# imu_shield.net
KiCad netlist of a schematic drawn in EAGLE
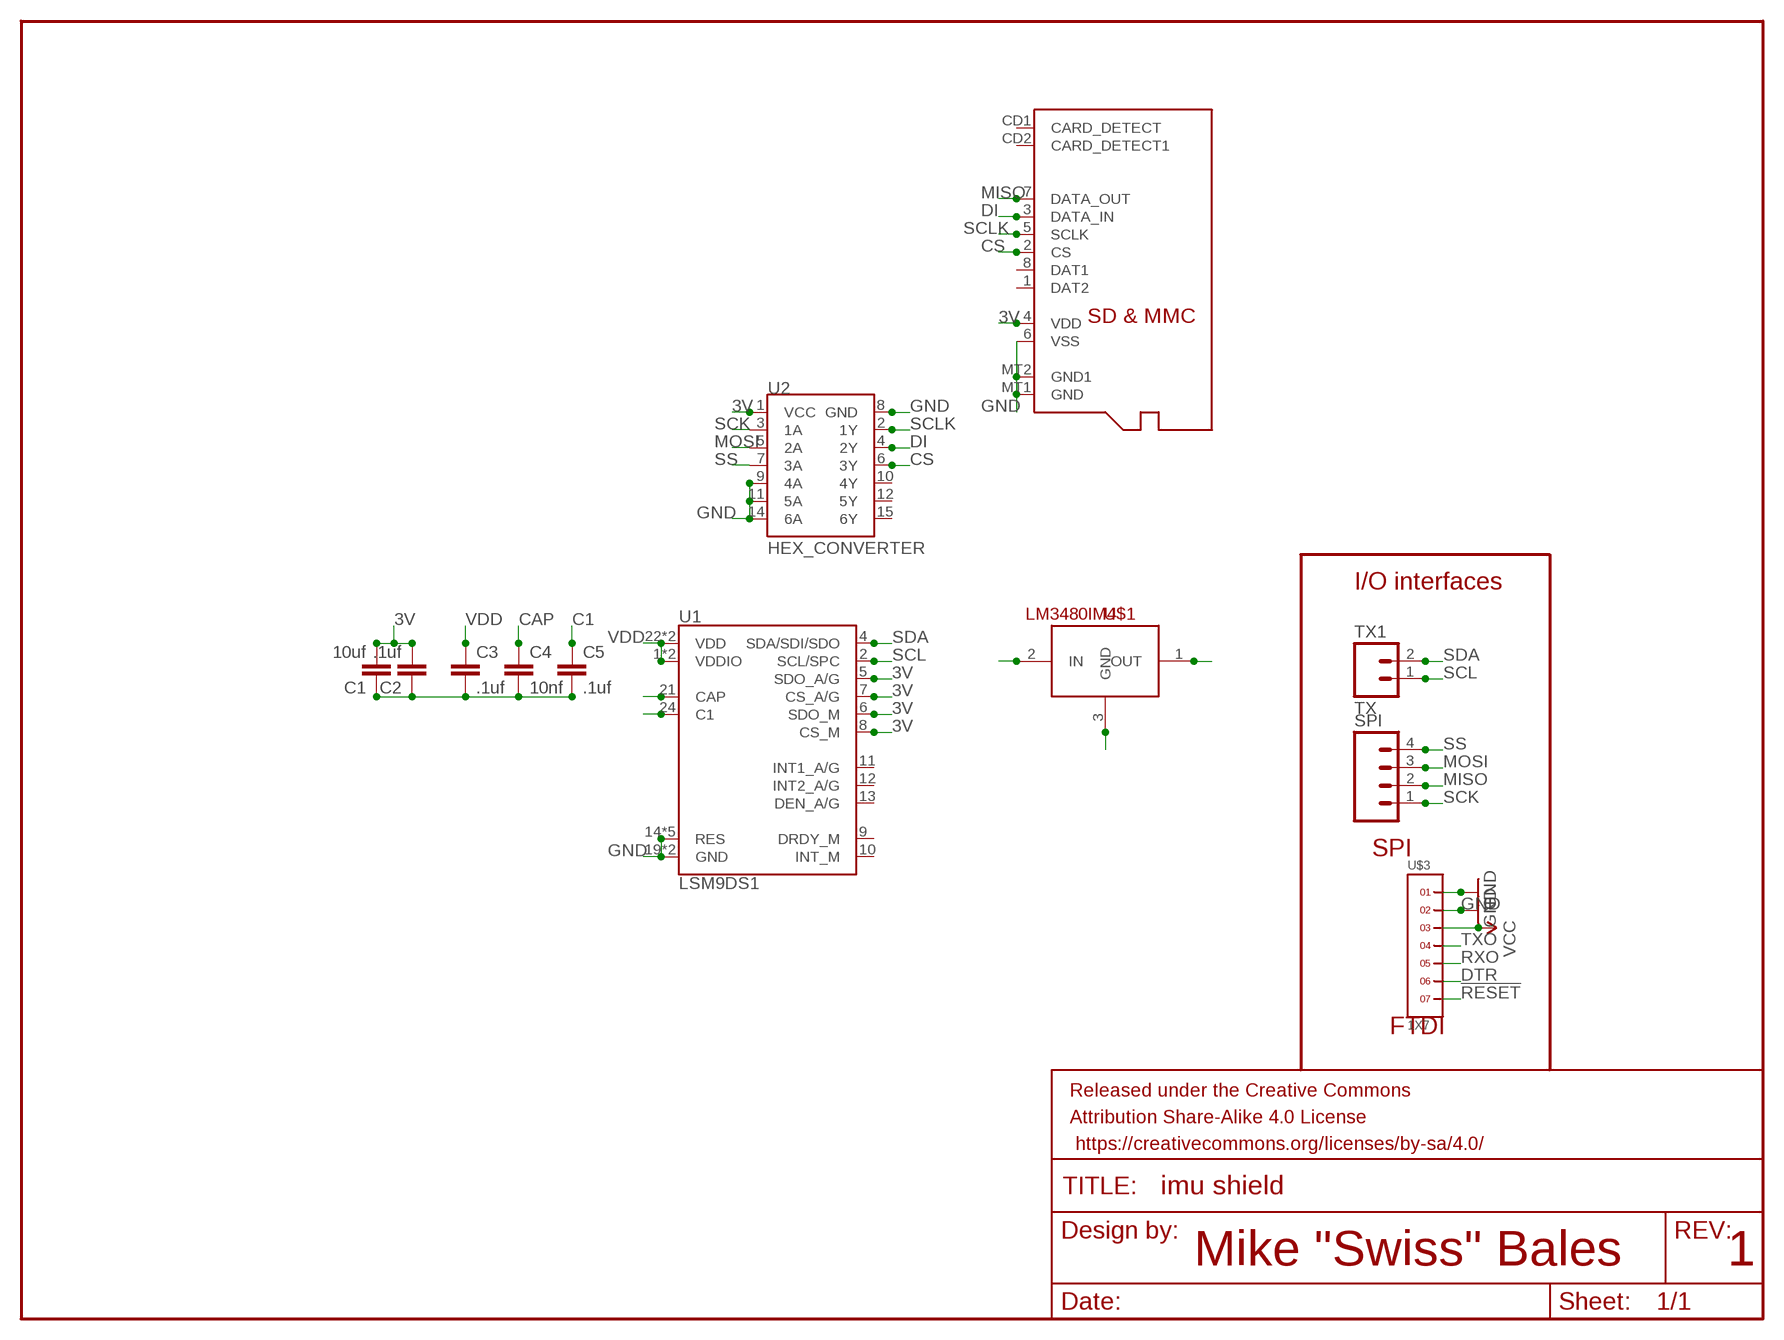
[diagram p0: schematic, sheet 1]

(export (version "E")
  (design (tool "Eeschema 10.0.6"))
  (components
    (comp (ref "C1")
      (value "10uf")
      (footprint "eagle-import:0805")
      (libsource (lib "eagle-import") (part "CAP0805"))
    )
    (comp (ref "C2")
      (value ".1uf")
      (footprint "eagle-import:0805")
      (libsource (lib "eagle-import") (part "CAP0805"))
    )
    (comp (ref "C3")
      (value ".1uf")
      (footprint "eagle-import:0805")
      (libsource (lib "eagle-import") (part "CAP0805"))
    )
    (comp (ref "C4")
      (value "10nf")
      (footprint "eagle-import:0805")
      (libsource (lib "eagle-import") (part "CAP0805"))
    )
    (comp (ref "C5")
      (value ".1uf")
      (footprint "eagle-import:0805")
      (libsource (lib "eagle-import") (part "CAP0805"))
    )
    (comp (ref "FRAME1")
      (value "FRAME-LETTER")
      (footprint "eagle-import:CREATIVE_COMMONS")
      (libsource (lib "eagle-import") (part "FRAME-LETTER"))
    )
    (comp (ref "SPI")
      (value "M04JST-PTH-VERT")
      (footprint "eagle-import:JST-4-PTH-VERT")
      (libsource (lib "eagle-import") (part "M04JST-PTH-VERT"))
    )
    (comp (ref "TX1")
      (value "TX")
      (footprint "eagle-import:JST-2-PTH-VERT")
      (libsource (lib "eagle-import") (part "M02JST-PTH-VERT"))
    )
    (comp (ref "U$1")
      (value "LM3480IM4")
      (footprint "eagle-import:SOT23-3")
      (libsource (lib "eagle-import") (part "LM3480IM4"))
    )
    (comp (ref "U$2")
      (value "MICROSD")
      (footprint "eagle-import:MICROSD")
      (libsource (lib "eagle-import") (part "MICROSD"))
    )
    (comp (ref "U$3")
      (value "1X7")
      (footprint "eagle-import:1X7")
      (libsource (lib "eagle-import") (part "1X7"))
    )
    (comp (ref "U1")
      (value "LSM9DS1")
      (footprint "eagle-import:LGA24-8X4")
      (libsource (lib "eagle-import") (part "LSM9DS1"))
    )
    (comp (ref "U2")
      (value "HEX_CONVERTER")
      (footprint "eagle-import:SO016")
      (libsource (lib "eagle-import") (part "HEX_CONVERTER"))
    )
  )
  (nets
    (net (code "1") (name "/3V") (class "Default")
      (node (ref "C1") (pin "2") (pinfunction "2_2") (pintype "passive"))
      (node (ref "C2") (pin "2") (pinfunction "2_2") (pintype "passive"))
      (node (ref "U$2") (pin "4") (pinfunction "VDD_4") (pintype "power_in"))
      (node (ref "U1") (pin "5") (pinfunction "SDO_A/G_5") (pintype "bidirectional"))
      (node (ref "U1") (pin "6") (pinfunction "SDO_M_6") (pintype "bidirectional"))
      (node (ref "U1") (pin "7") (pinfunction "CS_A/G_7") (pintype "bidirectional"))
      (node (ref "U1") (pin "8") (pinfunction "CS_M_8") (pintype "bidirectional"))
      (node (ref "U2") (pin "1") (pinfunction "VCC_1") (pintype "bidirectional"))
    )
    (net (code "2") (name "/C1") (class "Default")
      (node (ref "C5") (pin "1") (pinfunction "1_1") (pintype "passive"))
      (node (ref "U1") (pin "24") (pinfunction "C1_24") (pintype "bidirectional"))
    )
    (net (code "3") (name "/CAP") (class "Default")
      (node (ref "C4") (pin "1") (pinfunction "1_1") (pintype "passive"))
      (node (ref "U1") (pin "21") (pinfunction "CAP_21") (pintype "bidirectional"))
    )
    (net (code "4") (name "/CS") (class "Default")
      (node (ref "U$2") (pin "2") (pinfunction "CS_2") (pintype "input"))
      (node (ref "U2") (pin "6") (pinfunction "3Y_6") (pintype "bidirectional"))
    )
    (net (code "5") (name "/DI") (class "Default")
      (node (ref "U$2") (pin "3") (pinfunction "DATA_IN_3") (pintype "input"))
      (node (ref "U2") (pin "4") (pinfunction "2Y_4") (pintype "bidirectional"))
    )
    (net (code "6") (name "/DTR") (class "Default")
      (node (ref "U$3") (pin "6") (pinfunction "6_6") (pintype "bidirectional"))
    )
    (net (code "7") (name "/MISO") (class "Default")
      (node (ref "SPI") (pin "2") (pinfunction "2_2") (pintype "passive"))
      (node (ref "U$2") (pin "7") (pinfunction "DATA_OUT_7") (pintype "output"))
    )
    (net (code "8") (name "/MOSI") (class "Default")
      (node (ref "SPI") (pin "3") (pinfunction "3_3") (pintype "passive"))
      (node (ref "U2") (pin "5") (pinfunction "2A_5") (pintype "bidirectional"))
    )
    (net (code "9") (name "/RXO") (class "Default")
      (node (ref "U$3") (pin "5") (pinfunction "5_5") (pintype "bidirectional"))
    )
    (net (code "10") (name "/SCK") (class "Default")
      (node (ref "SPI") (pin "1") (pinfunction "1_1") (pintype "passive"))
      (node (ref "U2") (pin "3") (pinfunction "1A_3") (pintype "bidirectional"))
    )
    (net (code "11") (name "/SCL") (class "Default")
      (node (ref "TX1") (pin "1") (pinfunction "1_1") (pintype "passive"))
      (node (ref "U1") (pin "2") (pinfunction "SCL/SPC_2") (pintype "bidirectional"))
    )
    (net (code "12") (name "/SCLK") (class "Default")
      (node (ref "U$2") (pin "5") (pinfunction "SCLK_5") (pintype "input"))
      (node (ref "U2") (pin "2") (pinfunction "1Y_2") (pintype "bidirectional"))
    )
    (net (code "13") (name "/SDA") (class "Default")
      (node (ref "TX1") (pin "2") (pinfunction "2_2") (pintype "passive"))
      (node (ref "U1") (pin "4") (pinfunction "SDA/SDI/SDO_4") (pintype "bidirectional"))
    )
    (net (code "14") (name "/SS") (class "Default")
      (node (ref "SPI") (pin "4") (pinfunction "4_4") (pintype "passive"))
      (node (ref "U2") (pin "7") (pinfunction "3A_7") (pintype "bidirectional"))
    )
    (net (code "15") (name "/TXO") (class "Default")
      (node (ref "U$3") (pin "4") (pinfunction "4_4") (pintype "bidirectional"))
    )
    (net (code "16") (name "/VDD") (class "Default")
      (node (ref "C3") (pin "1") (pinfunction "1_1") (pintype "passive"))
      (node (ref "U$1") (pin "1") (pinfunction "OUT_1") (pintype "bidirectional"))
      (node (ref "U1") (pin "1") (pinfunction "VDDIO_1") (pintype "bidirectional"))
      (node (ref "U1") (pin "22") (pinfunction "VDD_22") (pintype "bidirectional"))
      (node (ref "U1") (pin "23") (pinfunction "VDD_23") (pintype "bidirectional"))
      (node (ref "U1") (pin "3") (pinfunction "VDDIO_3") (pintype "bidirectional"))
    )
    (net (code "17") (name "/~{RESET}") (class "Default")
      (node (ref "U$3") (pin "7") (pinfunction "7_7") (pintype "bidirectional"))
    )
    (net (code "18") (name "GND") (class "Default")
      (node (ref "U$1") (pin "3") (pinfunction "GND_3") (pintype "bidirectional"))
      (node (ref "U$2") (pin "6") (pinfunction "VSS_6") (pintype "power_in"))
      (node (ref "U$2") (pin "MT1") (pinfunction "GND_MT1") (pintype "power_in"))
      (node (ref "U$2") (pin "MT2") (pinfunction "GND1_MT2") (pintype "power_in"))
      (node (ref "U$3") (pin "1") (pinfunction "1_1") (pintype "bidirectional"))
      (node (ref "U$3") (pin "2") (pinfunction "2_2") (pintype "bidirectional"))
      (node (ref "U1") (pin "14") (pinfunction "RES_14") (pintype "bidirectional"))
      (node (ref "U1") (pin "15") (pinfunction "RES_15") (pintype "bidirectional"))
      (node (ref "U1") (pin "16") (pinfunction "RES_16") (pintype "bidirectional"))
      (node (ref "U1") (pin "17") (pinfunction "RES_17") (pintype "bidirectional"))
      (node (ref "U1") (pin "18") (pinfunction "RES_18") (pintype "bidirectional"))
      (node (ref "U1") (pin "19") (pinfunction "GND_19") (pintype "bidirectional"))
      (node (ref "U1") (pin "20") (pinfunction "GND_20") (pintype "bidirectional"))
      (node (ref "U2") (pin "11") (pinfunction "5A_11") (pintype "bidirectional"))
      (node (ref "U2") (pin "14") (pinfunction "6A_14") (pintype "bidirectional"))
      (node (ref "U2") (pin "8") (pinfunction "GND_8") (pintype "bidirectional"))
      (node (ref "U2") (pin "9") (pinfunction "4A_9") (pintype "bidirectional"))
    )
    (net (code "19") (name "Net-(C1-Pad1)") (class "Default")
      (node (ref "C1") (pin "1") (pinfunction "1_1") (pintype "passive"))
      (node (ref "C2") (pin "1") (pinfunction "1_1") (pintype "passive"))
      (node (ref "C3") (pin "2") (pinfunction "2_2") (pintype "passive"))
      (node (ref "C4") (pin "2") (pinfunction "2_2") (pintype "passive"))
      (node (ref "C5") (pin "2") (pinfunction "2_2") (pintype "passive"))
    )
    (net (code "20") (name "VCC") (class "Default")
      (node (ref "U$1") (pin "2") (pinfunction "IN_2") (pintype "bidirectional"))
      (node (ref "U$3") (pin "3") (pinfunction "3_3") (pintype "bidirectional"))
    )
    (net (code "21") (name "unconnected-(U$2-CARD_DETECT-PadCD1)") (class "Default")
      (node (ref "U$2") (pin "CD1") (pinfunction "CARD_DETECT_CD1") (pintype "passive"))
    )
    (net (code "22") (name "unconnected-(U$2-CARD_DETECT1-PadCD2)") (class "Default")
      (node (ref "U$2") (pin "CD2") (pinfunction "CARD_DETECT1_CD2") (pintype "passive"))
    )
    (net (code "23") (name "unconnected-(U$2-DAT1-Pad8)") (class "Default")
      (node (ref "U$2") (pin "8") (pinfunction "DAT1_8") (pintype "bidirectional"))
    )
    (net (code "24") (name "unconnected-(U$2-DAT2-Pad1)") (class "Default")
      (node (ref "U$2") (pin "1") (pinfunction "DAT2_1") (pintype "bidirectional"))
    )
    (net (code "25") (name "unconnected-(U1-DEN_A{slash}G-Pad13)") (class "Default")
      (node (ref "U1") (pin "13") (pinfunction "DEN_A/G_13") (pintype "bidirectional"))
    )
    (net (code "26") (name "unconnected-(U1-DRDY_M-Pad9)") (class "Default")
      (node (ref "U1") (pin "9") (pinfunction "DRDY_M_9") (pintype "bidirectional"))
    )
    (net (code "27") (name "unconnected-(U1-INT1_A{slash}G-Pad11)") (class "Default")
      (node (ref "U1") (pin "11") (pinfunction "INT1_A/G_11") (pintype "bidirectional"))
    )
    (net (code "28") (name "unconnected-(U1-INT2_A{slash}G-Pad12)") (class "Default")
      (node (ref "U1") (pin "12") (pinfunction "INT2_A/G_12") (pintype "bidirectional"))
    )
    (net (code "29") (name "unconnected-(U1-INT_M-Pad10)") (class "Default")
      (node (ref "U1") (pin "10") (pinfunction "INT_M_10") (pintype "bidirectional"))
    )
    (net (code "30") (name "unconnected-(U2-4Y-Pad10)") (class "Default")
      (node (ref "U2") (pin "10") (pinfunction "4Y_10") (pintype "bidirectional"))
    )
    (net (code "31") (name "unconnected-(U2-5Y-Pad12)") (class "Default")
      (node (ref "U2") (pin "12") (pinfunction "5Y_12") (pintype "bidirectional"))
    )
    (net (code "32") (name "unconnected-(U2-6Y-Pad15)") (class "Default")
      (node (ref "U2") (pin "15") (pinfunction "6Y_15") (pintype "bidirectional"))
    )
  )
)
